# 03_-_MCU.net
KiCad netlist of a schematic drawn in Altium Designer
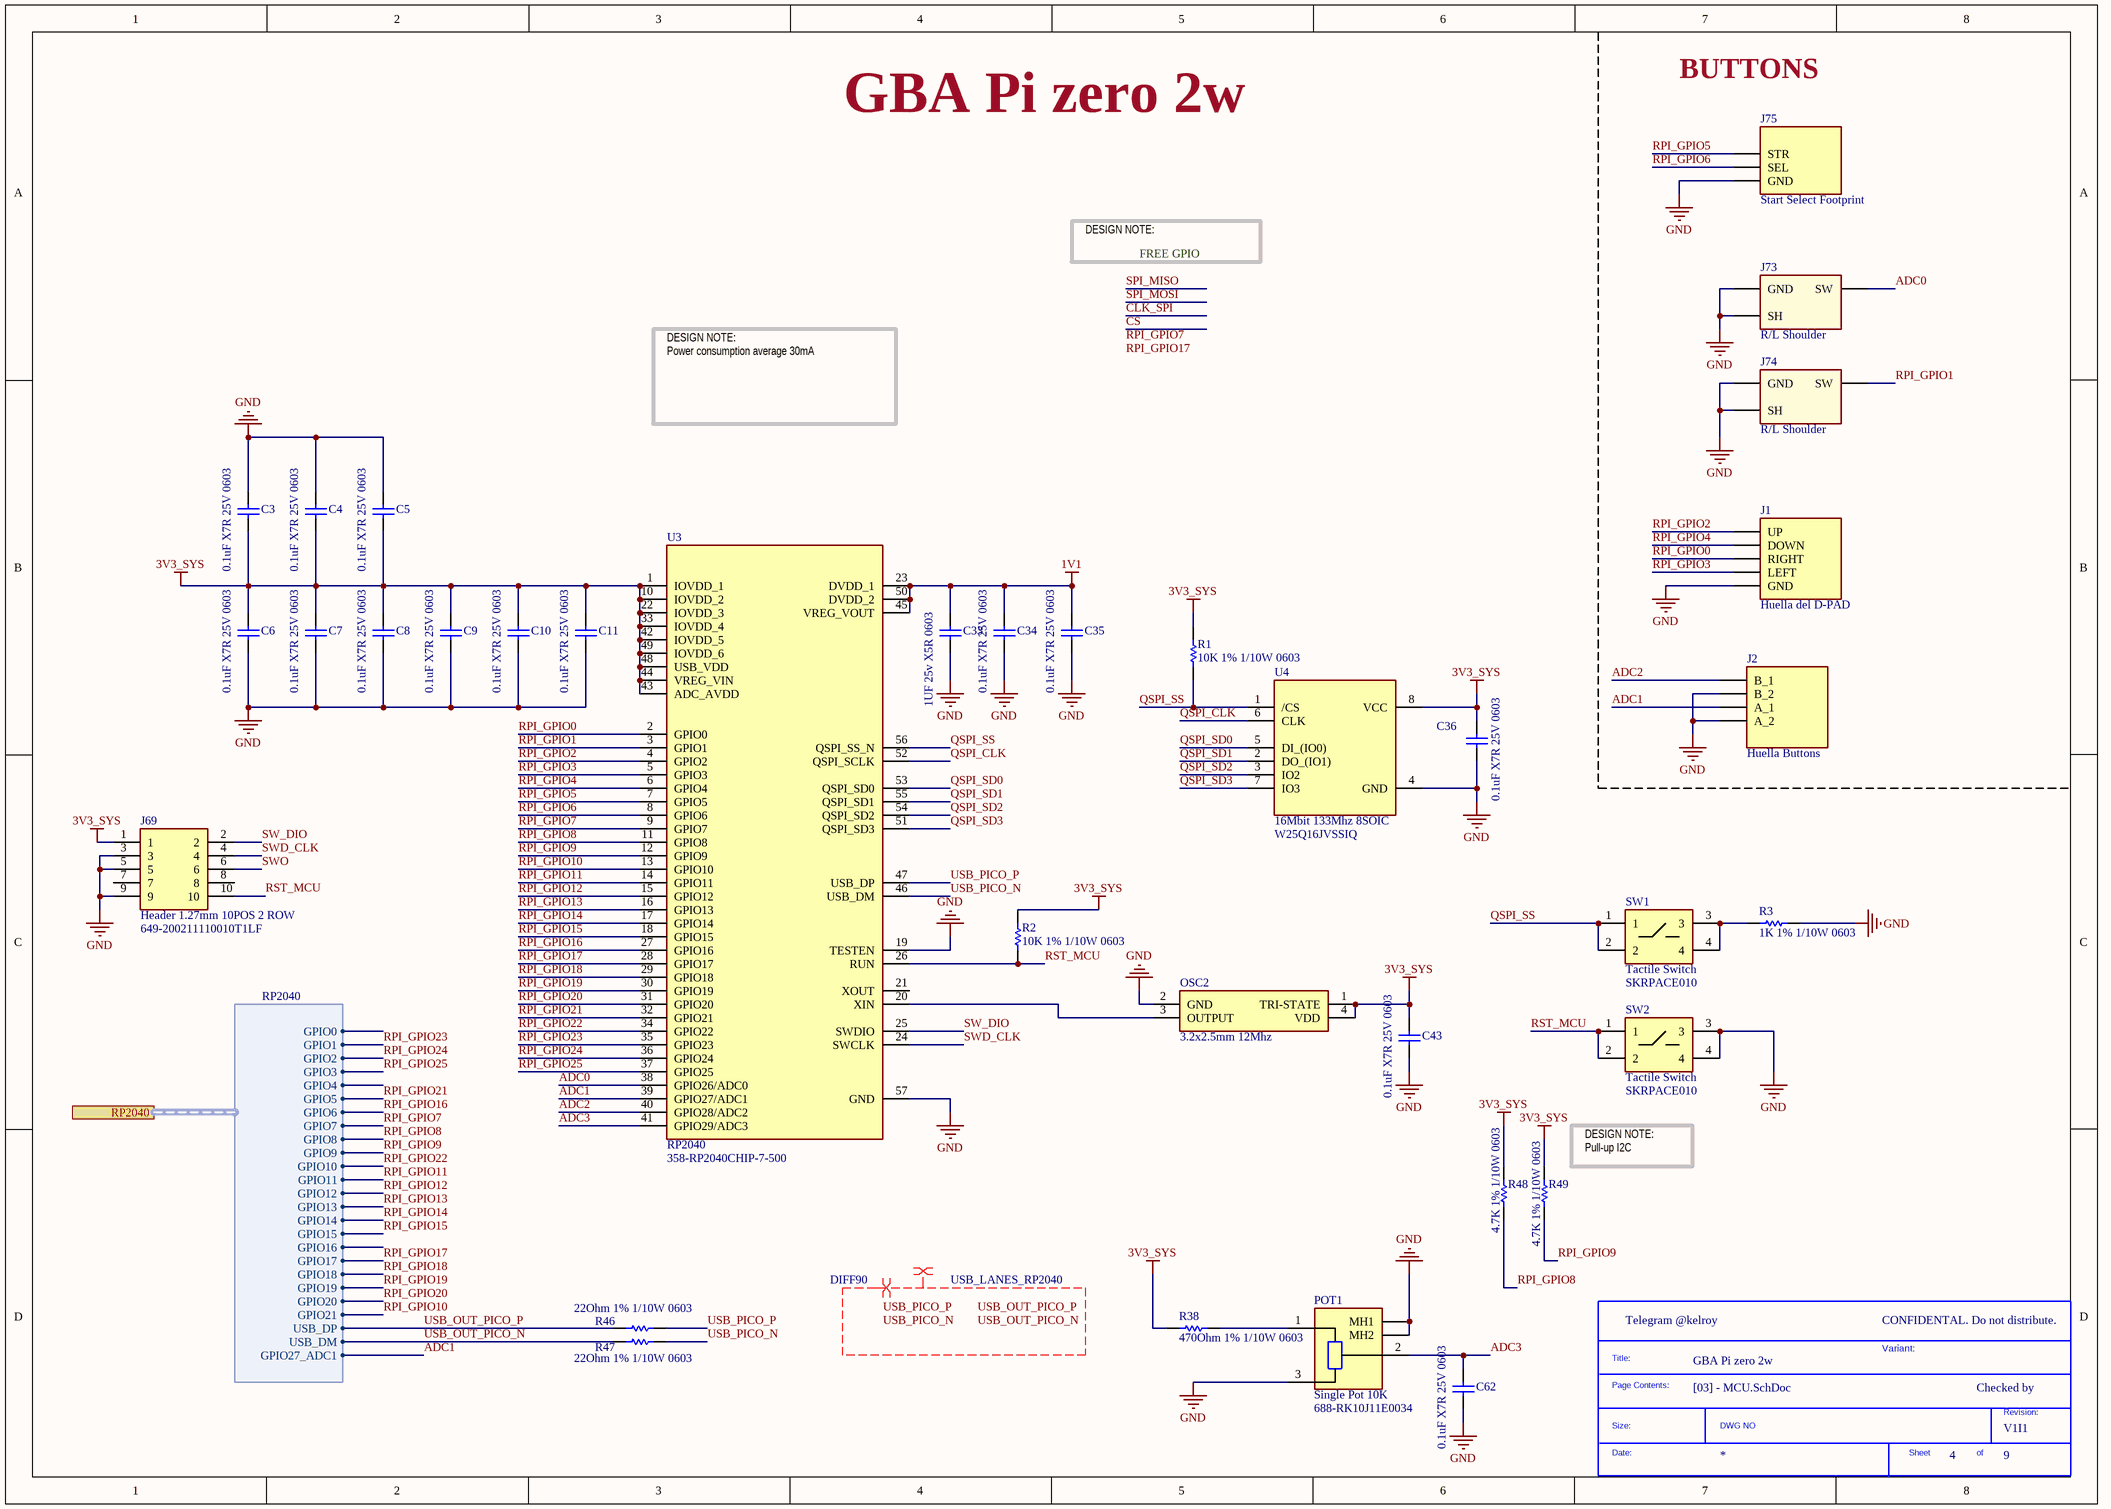
[diagram p0: [03] - MCU.SchDoc]

(export (version "E")
  (design (tool "Eeschema 10.0.6"))
  (components
    (comp (ref "C3")
      (value "0.1uF X7R 25V 0603")
      (footprint "C 0603/1608")
      (fields
        (field (name "MANUFACTURER") "Wurth Electronics")
        (field (name "MANUFACTURER PART NUMBER") "885012206071")
        (field (name "TOLERANCE") "10%")
      )
      (libsource (lib "altium-import") (part "root_1_885012206071_"))
    )
    (comp (ref "C4")
      (value "0.1uF X7R 25V 0603")
      (footprint "C 0603/1608")
      (fields
        (field (name "MANUFACTURER") "Wurth Electronics")
        (field (name "MANUFACTURER PART NUMBER") "885012206071")
        (field (name "TOLERANCE") "10%")
      )
      (libsource (lib "altium-import") (part "root_1_885012206071_"))
    )
    (comp (ref "C5")
      (value "0.1uF X7R 25V 0603")
      (footprint "C 0603/1608")
      (fields
        (field (name "MANUFACTURER") "Wurth Electronics")
        (field (name "MANUFACTURER PART NUMBER") "885012206071")
        (field (name "TOLERANCE") "10%")
      )
      (libsource (lib "altium-import") (part "root_1_885012206071_"))
    )
    (comp (ref "C6")
      (value "0.1uF X7R 25V 0603")
      (footprint "C 0603/1608")
      (fields
        (field (name "MANUFACTURER") "Wurth Electronics")
        (field (name "MANUFACTURER PART NUMBER") "885012206071")
        (field (name "TOLERANCE") "10%")
      )
      (libsource (lib "altium-import") (part "root_1_885012206071_"))
    )
    (comp (ref "C7")
      (value "0.1uF X7R 25V 0603")
      (footprint "C 0603/1608")
      (fields
        (field (name "MANUFACTURER") "Wurth Electronics")
        (field (name "MANUFACTURER PART NUMBER") "885012206071")
        (field (name "TOLERANCE") "10%")
      )
      (libsource (lib "altium-import") (part "root_1_885012206071_"))
    )
    (comp (ref "C8")
      (value "0.1uF X7R 25V 0603")
      (footprint "C 0603/1608")
      (fields
        (field (name "MANUFACTURER") "Wurth Electronics")
        (field (name "MANUFACTURER PART NUMBER") "885012206071")
        (field (name "TOLERANCE") "10%")
      )
      (libsource (lib "altium-import") (part "root_1_885012206071_"))
    )
    (comp (ref "C9")
      (value "0.1uF X7R 25V 0603")
      (footprint "C 0603/1608")
      (fields
        (field (name "MANUFACTURER") "Wurth Electronics")
        (field (name "MANUFACTURER PART NUMBER") "885012206071")
        (field (name "TOLERANCE") "10%")
      )
      (libsource (lib "altium-import") (part "root_1_885012206071_"))
    )
    (comp (ref "C10")
      (value "0.1uF X7R 25V 0603")
      (footprint "C 0603/1608")
      (fields
        (field (name "MANUFACTURER") "Wurth Electronics")
        (field (name "MANUFACTURER PART NUMBER") "885012206071")
        (field (name "TOLERANCE") "10%")
      )
      (libsource (lib "altium-import") (part "root_1_885012206071_"))
    )
    (comp (ref "C11")
      (value "0.1uF X7R 25V 0603")
      (footprint "C 0603/1608")
      (fields
        (field (name "MANUFACTURER") "Wurth Electronics")
        (field (name "MANUFACTURER PART NUMBER") "885012206071")
        (field (name "TOLERANCE") "10%")
      )
      (libsource (lib "altium-import") (part "root_1_885012206071_"))
    )
    (comp (ref "C33")
      (value "1UF 25v X5R 0603")
      (footprint "C 0603/1608")
      (description "CAP CER 1UF 25V X5R 0603")
      (fields
        (field (name "MANUFACTURER") "Yageo")
        (field (name "MANUFACTURER PART NUMBER") "CC0603KRX5R8BB105")
      )
      (libsource (lib "CM3Board_V1I2") (part "CC0603KRX5R8BB105"))
    )
    (comp (ref "C34")
      (value "0.1uF X7R 25V 0603")
      (footprint "C 0603/1608")
      (fields
        (field (name "MANUFACTURER") "Wurth Electronics")
        (field (name "MANUFACTURER PART NUMBER") "885012206071")
        (field (name "TOLERANCE") "10%")
      )
      (libsource (lib "altium-import") (part "root_1_885012206071_"))
    )
    (comp (ref "C35")
      (value "0.1uF X7R 25V 0603")
      (footprint "C 0603/1608")
      (fields
        (field (name "MANUFACTURER") "Wurth Electronics")
        (field (name "MANUFACTURER PART NUMBER") "885012206071")
        (field (name "TOLERANCE") "10%")
      )
      (libsource (lib "altium-import") (part "root_1_885012206071_"))
    )
    (comp (ref "C36")
      (value "0.1uF X7R 25V 0603")
      (footprint "C 0603/1608")
      (fields
        (field (name "MANUFACTURER") "Wurth Electronics")
        (field (name "MANUFACTURER PART NUMBER") "885012206071")
        (field (name "TOLERANCE") "10%")
      )
      (libsource (lib "altium-import") (part "root_1_885012206071_"))
    )
    (comp (ref "C43")
      (value "0.1uF X7R 25V 0603")
      (footprint "C 0603/1608")
      (fields
        (field (name "MANUFACTURER") "Wurth Electronics")
        (field (name "MANUFACTURER PART NUMBER") "885012206071")
        (field (name "TOLERANCE") "10%")
      )
      (libsource (lib "altium-import") (part "root_1_885012206071_"))
    )
    (comp (ref "C62")
      (value "0.1uF X7R 25V 0603")
      (footprint "C 0603/1608")
      (fields
        (field (name "MANUFACTURER") "Wurth Electronics")
        (field (name "MANUFACTURER PART NUMBER") "885012206071")
        (field (name "TOLERANCE") "10%")
      )
      (libsource (lib "altium-import") (part "root_1_885012206071_"))
    )
    (comp (ref "J1") (value "Huella del D-PAD") (footprint "D-PAD") (libsource (lib "GBA") (part "D_PAD")))
    (comp (ref "J2")
      (value "Huella Buttons")
      (footprint "AB_BUTTON")
      (libsource (lib "GBA") (part "BUTTONS"))
    )
    (comp (ref "J69")
      (value "Header 1.27mm 10POS 2 ROW")
      (footprint "20021111-00010T1LF")
      (description "Conn Unshrouded Header HDR 10 POS 1.27mm Solder ST Thru-Hole Tube")
      (fields (field (name "SUPPLIER PART NUMBER 1") "649-200211110010T1LF"))
      (libsource (lib "NtentePoC") (part "20021111-00010T1LF"))
    )
    (comp (ref "J73")
      (value "R/L Shoulder")
      (footprint "SHOULDER_BUTTON")
      (description "Buy on Aliexpress")
      (libsource (lib "GBA") (part "L/R Shoulder"))
    )
    (comp (ref "J74")
      (value "R/L Shoulder")
      (footprint "SHOULDER_BUTTON")
      (description "Buy on Aliexpress")
      (libsource (lib "GBA") (part "L/R Shoulder"))
    )
    (comp (ref "J75")
      (value "Start Select Footprint")
      (footprint "START SELECT FOOTPRINT")
      (description "Start Select")
      (libsource (lib "GBA") (part "START_SELECT"))
    )
    (comp (ref "OSC2")
      (value "3.2x2.5mm 12Mhz")
      (footprint "ECS3225MV120BNTR")
      (description "Oscillator XO 12MHz ±50ppm 15pF HCMOS 55% 1.8V/2.5V/3.3V 4-Pin Mini-CSMD T/R")
      (fields
        (field (name "MANUFACTURER") "ECS International")
        (field (name "MANUFACTURER PART NUMBER") "ECS-3225MV-120-BN-TR")
      )
      (libsource (lib "GBA") (part "ECS-3225MV-120-BN-TR"))
    )
    (comp (ref "POT1")
      (value "Single Pot 10K")
      (footprint "RK10J11E0034")
      (description "Res POT 10K Ohm 30% 3/100W 1(Elec)/1(Mech)Turn (14 X 13 X 3.8mm) Pin Thru-Hole")
      (fields
        (field (name "MANUFACTURER") "Alps Electric")
        (field (name "MANUFACTURER PART NUMBER") "RK10J11E0034")
        (field (name "SUPPLIER PART NUMBER 1") "688-RK10J11E0034")
      )
      (libsource (lib "GBA") (part "RK10J11E0034"))
    )
    (comp (ref "R1")
      (value "10K 1% 1/10W 0603")
      (footprint "R 0603/1608")
      (description "RES SMD 10K OHM 1% 1/10W 0603")
      (fields
        (field (name "MANUFACTURER") "Yageo")
        (field (name "MANUFACTURER PART NUMBER") "RC0603FR-0710KL")
      )
      (libsource (lib "GBA") (part "RC0603FR-0710KL"))
    )
    (comp (ref "R2")
      (value "10K 1% 1/10W 0603")
      (footprint "R 0603/1608")
      (description "RES SMD 10K OHM 1% 1/10W 0603")
      (fields
        (field (name "MANUFACTURER") "Yageo")
        (field (name "MANUFACTURER PART NUMBER") "RC0603FR-0710KL")
      )
      (libsource (lib "GBA") (part "RC0603FR-0710KL"))
    )
    (comp (ref "R3")
      (value "1K 1% 1/10W 0603")
      (footprint "R 0603/1608")
      (description "RES SMD 1K OHM 1% 1/10W 0603")
      (fields
        (field (name "MANUFACTURER") "Yageo")
        (field (name "MANUFACTURER PART NUMBER") "RC0603FR-071KL")
      )
      (libsource (lib "CM3Board_V1I2") (part "RC0603FR-071KL"))
    )
    (comp (ref "R38")
      (value "470Ohm 1% 1/10W 0603")
      (footprint "R 0603/1608")
      (description "RES SMD 470 OHM 1% 1/10W 0603")
      (fields
        (field (name "MANUFACTURER") "Yageo")
        (field (name "MANUFACTURER PART NUMBER") "RC0603FR-07470RL")
      )
      (libsource (lib "CM3Board_V1I2") (part "RC0603FR-07470RL"))
    )
    (comp (ref "R46")
      (value "22Ohm 1% 1/10W 0603")
      (footprint "R 0603/1608")
      (description "RES SMD 22 OHM 1% 1/10W 0603")
      (fields
        (field (name "MANUFACTURER") "Yageo")
        (field (name "MANUFACTURER PART NUMBER") "RC0603FR-0722RL")
      )
      (libsource (lib "CM3Board_V1I2") (part "RC0603FR-0722RL"))
    )
    (comp (ref "R47")
      (value "22Ohm 1% 1/10W 0603")
      (footprint "R 0603/1608")
      (description "RES SMD 22 OHM 1% 1/10W 0603")
      (fields
        (field (name "MANUFACTURER") "Yageo")
        (field (name "MANUFACTURER PART NUMBER") "RC0603FR-0722RL")
      )
      (libsource (lib "CM3Board_V1I2") (part "RC0603FR-0722RL"))
    )
    (comp (ref "R48")
      (value "4.7K 1% 1/10W 0603")
      (footprint "R 0603/1608")
      (description "RES SMD 4.7K OHM 1% 1/10W 0603")
      (fields
        (field (name "MANUFACTURER") "Yageo")
        (field (name "MANUFACTURER PART NUMBER") "RC0603FR-074K7L")
      )
      (libsource (lib "CM3Board_V1I2") (part "RC0603FR-074K7L"))
    )
    (comp (ref "R49")
      (value "4.7K 1% 1/10W 0603")
      (footprint "R 0603/1608")
      (description "RES SMD 4.7K OHM 1% 1/10W 0603")
      (fields
        (field (name "MANUFACTURER") "Yageo")
        (field (name "MANUFACTURER PART NUMBER") "RC0603FR-074K7L")
      )
      (libsource (lib "CM3Board_V1I2") (part "RC0603FR-074K7L"))
    )
    (comp (ref "SW1")
      (value "Tactile Switch")
      (footprint "SKRPACE010")
      (description "Tactile Switches 4.2x3.2x2.5mm 260gf")
      (fields
        (field (name "MANUFACTURER") "Alps Electric")
        (field (name "MANUFACTURER PART NUMBER") "SKRPACE010")
        (field (name "SUPPLIER PART NUMBER 1") "SKRPACE010")
      )
      (libsource (lib "GBA") (part "SKRPACE010"))
    )
    (comp (ref "SW2")
      (value "Tactile Switch")
      (footprint "SKRPACE010")
      (description "Tactile Switches 4.2x3.2x2.5mm 260gf")
      (fields
        (field (name "MANUFACTURER") "Alps Electric")
        (field (name "MANUFACTURER PART NUMBER") "SKRPACE010")
        (field (name "SUPPLIER PART NUMBER 1") "SKRPACE010")
      )
      (libsource (lib "GBA") (part "SKRPACE010"))
    )
    (comp (ref "U3")
      (value "RP2040")
      (footprint "QFN40P700X700X90-57N-D")
      (description "RP2040 Raspberry pi Dual core M0")
      (fields
        (field (name "MANUFACTURER") "Raspberry Pi")
        (field (name "MANUFACTURER PART NUMBER") "RPICHIPRP2040-7-500")
        (field (name "SUPPLIER PART NUMBER 1") "358-RP2040CHIP-7-500")
      )
      (libsource (lib "GBA") (part "RPICHIPRP2040-7-500"))
    )
    (comp (ref "U4")
      (value "16Mbit 133Mhz 8SOIC")
      (footprint "SOIC127P790X216-8N")
      (description "ICFLASH16MBIT133MHZ8SOIC")
      (fields
        (field (name "MANUFACTURER") "Winbond")
        (field (name "MANUFACTURER PART NUMBER") "W25Q16JVSSIQ")
        (field (name "SUPPLIER PART NUMBER 1") "W25Q16JVSSIQ")
      )
      (libsource (lib "GBA") (part "W25Q16JVSSIQ"))
    )
  )
  (nets
    (net (code "2") (name "/ADC0") (class "Default")
      (node (ref "J73") (pin "SW") (pinfunction "SW_SW") (pintype "passive"))
      (node (ref "U3") (pin "38") (pinfunction "GPIO26/ADC0_38") (pintype "passive"))
    )
    (net (code "3") (name "/ADC1") (class "Default")
      (node (ref "J2") (pin "A_1") (pinfunction "A_1_A_1") (pintype "passive"))
      (node (ref "U3") (pin "39") (pinfunction "GPIO27/ADC1_39") (pintype "passive"))
    )
    (net (code "4") (name "/ADC2") (class "Default")
      (node (ref "J2") (pin "B_1") (pinfunction "B_1_B_1") (pintype "passive"))
      (node (ref "U3") (pin "40") (pinfunction "GPIO28/ADC2_40") (pintype "passive"))
    )
    (net (code "5") (name "/ADC3") (class "Default")
      (node (ref "C62") (pin "1") (pinfunction "1_1") (pintype "passive"))
      (node (ref "POT1") (pin "2") (pinfunction "2_2") (pintype "passive"))
      (node (ref "U3") (pin "41") (pinfunction "GPIO29/ADC3_41") (pintype "passive"))
    )
    (net (code "8") (name "/QSPI_CLK") (class "Default")
      (node (ref "U3") (pin "52") (pinfunction "QSPI_SCLK_52") (pintype "passive"))
      (node (ref "U4") (pin "6") (pinfunction "CLK_6") (pintype "passive"))
    )
    (net (code "9") (name "/QSPI_SD0") (class "Default")
      (node (ref "U3") (pin "53") (pinfunction "QSPI_SD0_53") (pintype "passive"))
      (node (ref "U4") (pin "5") (pinfunction "DI_(IO0)_5") (pintype "passive"))
    )
    (net (code "10") (name "/QSPI_SD1") (class "Default")
      (node (ref "U3") (pin "55") (pinfunction "QSPI_SD1_55") (pintype "passive"))
      (node (ref "U4") (pin "2") (pinfunction "DO_(IO1)_2") (pintype "passive"))
    )
    (net (code "11") (name "/QSPI_SD2") (class "Default")
      (node (ref "U3") (pin "54") (pinfunction "QSPI_SD2_54") (pintype "passive"))
      (node (ref "U4") (pin "3") (pinfunction "IO2_3") (pintype "passive"))
    )
    (net (code "12") (name "/QSPI_SD3") (class "Default")
      (node (ref "U3") (pin "51") (pinfunction "QSPI_SD3_51") (pintype "passive"))
      (node (ref "U4") (pin "7") (pinfunction "IO3_7") (pintype "passive"))
    )
    (net (code "13") (name "/QSPI_SS") (class "Default")
      (node (ref "R1") (pin "1") (pinfunction "1_1") (pintype "passive"))
      (node (ref "SW1") (pin "1") (pinfunction "1_1") (pintype "passive"))
      (node (ref "SW1") (pin "2") (pinfunction "2_2") (pintype "passive"))
      (node (ref "U3") (pin "56") (pinfunction "QSPI_SS_N_56") (pintype "passive"))
      (node (ref "U4") (pin "1") (pinfunction "/CS_1") (pintype "passive"))
    )
    (net (code "14") (name "/RPI_GPIO0") (class "Default")
      (node (ref "J1") (pin "RIGHT") (pinfunction "RIGHT_RIGHT") (pintype "passive"))
      (node (ref "U3") (pin "2") (pinfunction "GPIO0_2") (pintype "passive"))
    )
    (net (code "15") (name "/RPI_GPIO1") (class "Default")
      (node (ref "J74") (pin "SW") (pinfunction "SW_SW") (pintype "passive"))
      (node (ref "U3") (pin "3") (pinfunction "GPIO1_3") (pintype "passive"))
    )
    (net (code "16") (name "/RPI_GPIO2") (class "Default")
      (node (ref "J1") (pin "UP") (pinfunction "UP_UP") (pintype "passive"))
      (node (ref "U3") (pin "4") (pinfunction "GPIO2_4") (pintype "passive"))
    )
    (net (code "17") (name "/RPI_GPIO3") (class "Default")
      (node (ref "J1") (pin "LEFT") (pinfunction "LEFT_LEFT") (pintype "passive"))
      (node (ref "U3") (pin "5") (pinfunction "GPIO3_5") (pintype "passive"))
    )
    (net (code "18") (name "/RPI_GPIO4") (class "Default")
      (node (ref "J1") (pin "DOWN") (pinfunction "DOWN_DOWN") (pintype "passive"))
      (node (ref "U3") (pin "6") (pinfunction "GPIO4_6") (pintype "passive"))
    )
    (net (code "19") (name "/RPI_GPIO5") (class "Default")
      (node (ref "J75") (pin "STR") (pinfunction "STR_STR") (pintype "passive"))
      (node (ref "U3") (pin "7") (pinfunction "GPIO5_7") (pintype "passive"))
    )
    (net (code "20") (name "/RPI_GPIO6") (class "Default")
      (node (ref "J75") (pin "SEL") (pinfunction "SEL_SEL") (pintype "passive"))
      (node (ref "U3") (pin "8") (pinfunction "GPIO6_8") (pintype "passive"))
    )
    (net (code "21") (name "/RPI_GPIO7") (class "Default")
      (node (ref "U3") (pin "9") (pinfunction "GPIO7_9") (pintype "passive"))
    )
    (net (code "22") (name "/RPI_GPIO8") (class "Default")
      (node (ref "R48") (pin "1") (pinfunction "1_1") (pintype "passive"))
      (node (ref "U3") (pin "11") (pinfunction "GPIO8_11") (pintype "passive"))
    )
    (net (code "23") (name "/RPI_GPIO9") (class "Default")
      (node (ref "R49") (pin "1") (pinfunction "1_1") (pintype "passive"))
      (node (ref "U3") (pin "12") (pinfunction "GPIO9_12") (pintype "passive"))
    )
    (net (code "24") (name "/RPI_GPIO10") (class "Default")
      (node (ref "U3") (pin "13") (pinfunction "GPIO10_13") (pintype "passive"))
    )
    (net (code "25") (name "/RPI_GPIO11") (class "Default")
      (node (ref "U3") (pin "14") (pinfunction "GPIO11_14") (pintype "passive"))
    )
    (net (code "26") (name "/RPI_GPIO12") (class "Default")
      (node (ref "U3") (pin "15") (pinfunction "GPIO12_15") (pintype "passive"))
    )
    (net (code "27") (name "/RPI_GPIO13") (class "Default")
      (node (ref "U3") (pin "16") (pinfunction "GPIO13_16") (pintype "passive"))
    )
    (net (code "28") (name "/RPI_GPIO14") (class "Default")
      (node (ref "U3") (pin "17") (pinfunction "GPIO14_17") (pintype "passive"))
    )
    (net (code "29") (name "/RPI_GPIO15") (class "Default")
      (node (ref "U3") (pin "18") (pinfunction "GPIO15_18") (pintype "passive"))
    )
    (net (code "30") (name "/RPI_GPIO16") (class "Default")
      (node (ref "U3") (pin "27") (pinfunction "GPIO16_27") (pintype "passive"))
    )
    (net (code "31") (name "/RPI_GPIO17") (class "Default")
      (node (ref "U3") (pin "28") (pinfunction "GPIO17_28") (pintype "passive"))
    )
    (net (code "32") (name "/RPI_GPIO18") (class "Default")
      (node (ref "U3") (pin "29") (pinfunction "GPIO18_29") (pintype "passive"))
    )
    (net (code "33") (name "/RPI_GPIO19") (class "Default")
      (node (ref "U3") (pin "30") (pinfunction "GPIO19_30") (pintype "passive"))
    )
    (net (code "34") (name "/RPI_GPIO20") (class "Default")
      (node (ref "U3") (pin "31") (pinfunction "GPIO20_31") (pintype "passive"))
    )
    (net (code "35") (name "/RPI_GPIO21") (class "Default")
      (node (ref "U3") (pin "32") (pinfunction "GPIO21_32") (pintype "passive"))
    )
    (net (code "36") (name "/RPI_GPIO22") (class "Default")
      (node (ref "U3") (pin "34") (pinfunction "GPIO22_34") (pintype "passive"))
    )
    (net (code "37") (name "/RPI_GPIO23") (class "Default")
      (node (ref "U3") (pin "35") (pinfunction "GPIO23_35") (pintype "passive"))
    )
    (net (code "38") (name "/RPI_GPIO24") (class "Default")
      (node (ref "U3") (pin "36") (pinfunction "GPIO24_36") (pintype "passive"))
    )
    (net (code "39") (name "/RPI_GPIO25") (class "Default")
      (node (ref "U3") (pin "37") (pinfunction "GPIO25_37") (pintype "passive"))
    )
    (net (code "40") (name "/RST_MCU") (class "Default")
      (node (ref "J69") (pin "10") (pinfunction "10_10") (pintype "passive"))
      (node (ref "R2") (pin "1") (pinfunction "1_1") (pintype "passive"))
      (node (ref "SW2") (pin "1") (pinfunction "1_1") (pintype "passive"))
      (node (ref "SW2") (pin "2") (pinfunction "2_2") (pintype "passive"))
      (node (ref "U3") (pin "26") (pinfunction "RUN_26") (pintype "passive"))
    )
    (net (code "43") (name "/SWD_CLK") (class "Default")
      (node (ref "J69") (pin "4") (pinfunction "4_4") (pintype "passive"))
      (node (ref "U3") (pin "24") (pinfunction "SWCLK_24") (pintype "passive"))
    )
    (net (code "44") (name "/SWO") (class "Default")
      (node (ref "J69") (pin "6") (pinfunction "6_6") (pintype "passive"))
    )
    (net (code "45") (name "/SW_DIO") (class "Default")
      (node (ref "J69") (pin "2") (pinfunction "2_2") (pintype "passive"))
      (node (ref "U3") (pin "25") (pinfunction "SWDIO_25") (pintype "passive"))
    )
    (net (code "46") (name "/USB_OUT_PICO_N") (class "Default")
      (node (ref "R47") (pin "1") (pinfunction "1_1") (pintype "passive"))
    )
    (net (code "47") (name "/USB_OUT_PICO_P") (class "Default")
      (node (ref "R46") (pin "1") (pinfunction "1_1") (pintype "passive"))
    )
    (net (code "48") (name "/USB_PICO_N") (class "Default")
      (node (ref "R47") (pin "2") (pinfunction "2_2") (pintype "passive"))
      (node (ref "U3") (pin "46") (pinfunction "USB_DM_46") (pintype "passive"))
    )
    (net (code "49") (name "/USB_PICO_P") (class "Default")
      (node (ref "R46") (pin "2") (pinfunction "2_2") (pintype "passive"))
      (node (ref "U3") (pin "47") (pinfunction "USB_DP_47") (pintype "passive"))
    )
    (net (code "51") (name "1V1") (class "Default")
      (node (ref "C33") (pin "1") (pinfunction "1_1") (pintype "passive"))
      (node (ref "C34") (pin "1") (pinfunction "1_1") (pintype "passive"))
      (node (ref "C35") (pin "1") (pinfunction "1_1") (pintype "passive"))
      (node (ref "U3") (pin "23") (pinfunction "DVDD_1_23") (pintype "passive"))
      (node (ref "U3") (pin "45") (pinfunction "VREG_VOUT_45") (pintype "passive"))
      (node (ref "U3") (pin "50") (pinfunction "DVDD_2_50") (pintype "passive"))
    )
    (net (code "52") (name "3V3_SYS") (class "Default")
      (node (ref "C10") (pin "1") (pinfunction "1_1") (pintype "passive"))
      (node (ref "C11") (pin "1") (pinfunction "1_1") (pintype "passive"))
      (node (ref "C3") (pin "2") (pinfunction "2_2") (pintype "passive"))
      (node (ref "C36") (pin "1") (pinfunction "1_1") (pintype "passive"))
      (node (ref "C4") (pin "2") (pinfunction "2_2") (pintype "passive"))
      (node (ref "C43") (pin "1") (pinfunction "1_1") (pintype "passive"))
      (node (ref "C5") (pin "2") (pinfunction "2_2") (pintype "passive"))
      (node (ref "C6") (pin "1") (pinfunction "1_1") (pintype "passive"))
      (node (ref "C7") (pin "1") (pinfunction "1_1") (pintype "passive"))
      (node (ref "C8") (pin "1") (pinfunction "1_1") (pintype "passive"))
      (node (ref "C9") (pin "1") (pinfunction "1_1") (pintype "passive"))
      (node (ref "J69") (pin "1") (pinfunction "1_1") (pintype "passive"))
      (node (ref "OSC2") (pin "1") (pinfunction "TRI-STATE_1") (pintype "passive"))
      (node (ref "OSC2") (pin "4") (pinfunction "VDD_4") (pintype "passive"))
      (node (ref "R1") (pin "2") (pinfunction "2_2") (pintype "passive"))
      (node (ref "R2") (pin "2") (pinfunction "2_2") (pintype "passive"))
      (node (ref "R38") (pin "1") (pinfunction "1_1") (pintype "passive"))
      (node (ref "R48") (pin "2") (pinfunction "2_2") (pintype "passive"))
      (node (ref "R49") (pin "2") (pinfunction "2_2") (pintype "passive"))
      (node (ref "U3") (pin "1") (pinfunction "IOVDD_1_1") (pintype "passive"))
      (node (ref "U3") (pin "10") (pinfunction "IOVDD_2_10") (pintype "passive"))
      (node (ref "U3") (pin "22") (pinfunction "IOVDD_3_22") (pintype "passive"))
      (node (ref "U3") (pin "33") (pinfunction "IOVDD_4_33") (pintype "passive"))
      (node (ref "U3") (pin "42") (pinfunction "IOVDD_5_42") (pintype "passive"))
      (node (ref "U3") (pin "43") (pinfunction "ADC_AVDD_43") (pintype "passive"))
      (node (ref "U3") (pin "44") (pinfunction "VREG_VIN_44") (pintype "passive"))
      (node (ref "U3") (pin "48") (pinfunction "USB_VDD_48") (pintype "passive"))
      (node (ref "U3") (pin "49") (pinfunction "IOVDD_6_49") (pintype "passive"))
      (node (ref "U4") (pin "8") (pinfunction "VCC_8") (pintype "passive"))
    )
    (net (code "53") (name "GND") (class "Default")
      (node (ref "C10") (pin "2") (pinfunction "2_2") (pintype "passive"))
      (node (ref "C11") (pin "2") (pinfunction "2_2") (pintype "passive"))
      (node (ref "C3") (pin "1") (pinfunction "1_1") (pintype "passive"))
      (node (ref "C33") (pin "2") (pinfunction "2_2") (pintype "passive"))
      (node (ref "C34") (pin "2") (pinfunction "2_2") (pintype "passive"))
      (node (ref "C35") (pin "2") (pinfunction "2_2") (pintype "passive"))
      (node (ref "C36") (pin "2") (pinfunction "2_2") (pintype "passive"))
      (node (ref "C4") (pin "1") (pinfunction "1_1") (pintype "passive"))
      (node (ref "C43") (pin "2") (pinfunction "2_2") (pintype "passive"))
      (node (ref "C5") (pin "1") (pinfunction "1_1") (pintype "passive"))
      (node (ref "C6") (pin "2") (pinfunction "2_2") (pintype "passive"))
      (node (ref "C62") (pin "2") (pinfunction "2_2") (pintype "passive"))
      (node (ref "C7") (pin "2") (pinfunction "2_2") (pintype "passive"))
      (node (ref "C8") (pin "2") (pinfunction "2_2") (pintype "passive"))
      (node (ref "C9") (pin "2") (pinfunction "2_2") (pintype "passive"))
      (node (ref "J1") (pin "GND") (pinfunction "GND_GND") (pintype "passive"))
      (node (ref "J2") (pin "A_2") (pinfunction "A_2_A_2") (pintype "passive"))
      (node (ref "J2") (pin "B_2") (pinfunction "B_2_B_2") (pintype "passive"))
      (node (ref "J69") (pin "3") (pinfunction "3_3") (pintype "passive"))
      (node (ref "J69") (pin "5") (pinfunction "5_5") (pintype "passive"))
      (node (ref "J69") (pin "9") (pinfunction "9_9") (pintype "passive"))
      (node (ref "J73") (pin "GND") (pinfunction "GND_GND") (pintype "passive"))
      (node (ref "J73") (pin "SH") (pinfunction "SH_SH") (pintype "passive"))
      (node (ref "J74") (pin "GND") (pinfunction "GND_GND") (pintype "passive"))
      (node (ref "J74") (pin "SH") (pinfunction "SH_SH") (pintype "passive"))
      (node (ref "J75") (pin "GND") (pinfunction "GND_GND") (pintype "passive"))
      (node (ref "OSC2") (pin "2") (pinfunction "GND_2") (pintype "passive"))
      (node (ref "POT1") (pin "3") (pinfunction "3_3") (pintype "passive"))
      (node (ref "POT1") (pin "MH1") (pinfunction "MH1_MH1") (pintype "passive"))
      (node (ref "POT1") (pin "MH2") (pinfunction "MH2_MH2") (pintype "passive"))
      (node (ref "R3") (pin "1") (pinfunction "1_1") (pintype "passive"))
      (node (ref "SW2") (pin "3") (pinfunction "3_3") (pintype "passive"))
      (node (ref "SW2") (pin "4") (pinfunction "4_4") (pintype "passive"))
      (node (ref "U3") (pin "19") (pinfunction "TESTEN_19") (pintype "passive"))
      (node (ref "U3") (pin "57") (pinfunction "GND_57") (pintype "passive"))
      (node (ref "U4") (pin "4") (pinfunction "GND_4") (pintype "passive"))
    )
    (net (code "54") (name "Net-(OSC2-OUTPUT)") (class "Default")
      (node (ref "OSC2") (pin "3") (pinfunction "OUTPUT_3") (pintype "passive"))
      (node (ref "U3") (pin "20") (pinfunction "XIN_20") (pintype "passive"))
    )
    (net (code "55") (name "Net-(POT1-Pad1)") (class "Default")
      (node (ref "POT1") (pin "1") (pinfunction "1_1") (pintype "passive"))
      (node (ref "R38") (pin "2") (pinfunction "2_2") (pintype "passive"))
    )
    (net (code "56") (name "Net-(R3-Pad2)") (class "Default")
      (node (ref "R3") (pin "2") (pinfunction "2_2") (pintype "passive"))
      (node (ref "SW1") (pin "3") (pinfunction "3_3") (pintype "passive"))
      (node (ref "SW1") (pin "4") (pinfunction "4_4") (pintype "passive"))
    )
    (net (code "57") (name "unconnected-(J69-Pad7)") (class "Default")
      (node (ref "J69") (pin "7") (pinfunction "7_7") (pintype "passive"))
    )
    (net (code "58") (name "unconnected-(J69-Pad8)") (class "Default")
      (node (ref "J69") (pin "8") (pinfunction "8_8") (pintype "passive"))
    )
    (net (code "59") (name "unconnected-(U3-XOUT-Pad21)") (class "Default")
      (node (ref "U3") (pin "21") (pinfunction "XOUT_21") (pintype "passive"))
    )
  )
)
